# WIZ850io_SCH_V100.net
KiCad netlist of a schematic drawn in Altium Designer
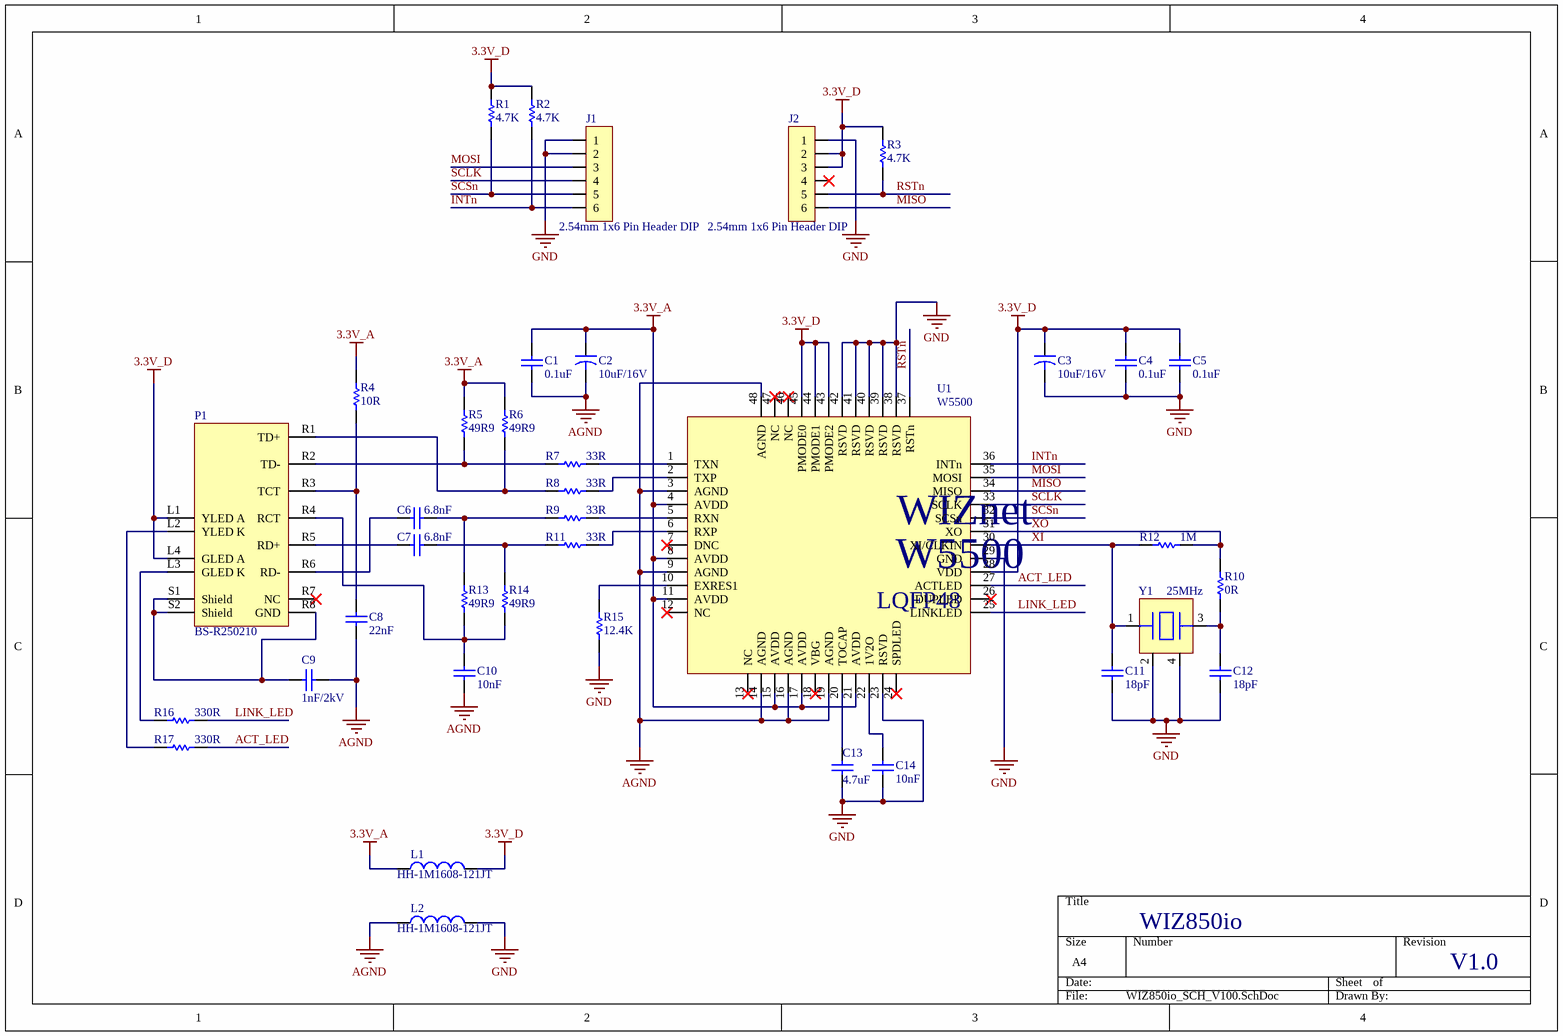
[diagram p0: WIZ850io_SCH_V100.SchDoc]

(export (version "E")
  (design (tool "Eeschema 10.0.6"))
  (components
    (comp (ref "C1")
      (value "0.1uF")
      (footprint "CAP-0402")
      (description "Ceramic CAP 0402(1005)")
      (libsource (lib "Scott_lib") (part "CAP-0402"))
    )
    (comp (ref "C2")
      (value "10uF/16V")
      (footprint "CAP-A Size")
      (description "Tantla CAP A Size EIA/IECQ 3216")
      (libsource (lib "Scott_lib") (part "CAP-A Size"))
    )
    (comp (ref "C3")
      (value "10uF/16V")
      (footprint "CAP-A Size")
      (description "Tantla CAP A Size EIA/IECQ 3216")
      (libsource (lib "Scott_lib") (part "CAP-A Size"))
    )
    (comp (ref "C4")
      (value "0.1uF")
      (footprint "CAP-0402")
      (description "Ceramic CAP 0402(1005)")
      (libsource (lib "Scott_lib") (part "CAP-0402"))
    )
    (comp (ref "C5")
      (value "0.1uF")
      (footprint "CAP-0402")
      (description "Ceramic CAP 0402(1005)")
      (libsource (lib "Scott_lib") (part "CAP-0402"))
    )
    (comp (ref "C6")
      (value "6.8nF")
      (footprint "CAP-0402")
      (description "Ceramic CAP 0402(1005)")
      (libsource (lib "Scott_lib") (part "CAP-0402"))
    )
    (comp (ref "C7")
      (value "6.8nF")
      (footprint "CAP-0402")
      (description "Ceramic CAP 0402(1005)")
      (libsource (lib "Scott_lib") (part "CAP-0402"))
    )
    (comp (ref "C8")
      (value "22nF")
      (footprint "CAP-0402")
      (description "Ceramic CAP 0402(1005)")
      (libsource (lib "Scott_lib") (part "CAP-0402"))
    )
    (comp (ref "C9")
      (value "1nF/2kV")
      (footprint "CAP-1808")
      (description "Ceramic CAP 1808(4520)")
      (libsource (lib "Scott_lib") (part "CAP-1808"))
    )
    (comp (ref "C10")
      (value "10nF")
      (footprint "CAP-0402")
      (description "Ceramic CAP 0402(1005)")
      (libsource (lib "Scott_lib") (part "CAP-0402"))
    )
    (comp (ref "C11")
      (value "18pF")
      (footprint "CAP-0402")
      (description "Ceramic CAP 0402(1005)")
      (libsource (lib "Scott_lib") (part "CAP-0402"))
    )
    (comp (ref "C12")
      (value "18pF")
      (footprint "CAP-0402")
      (description "Ceramic CAP 0402(1005)")
      (libsource (lib "Scott_lib") (part "CAP-0402"))
    )
    (comp (ref "C13")
      (value "4.7uF")
      (footprint "CAP-0805")
      (description "Ceramic CAP 0402(1005)")
      (libsource (lib "Scott_lib") (part "CAP-0402"))
    )
    (comp (ref "C14")
      (value "10nF")
      (footprint "CAP-0402")
      (description "Ceramic CAP 0805(2012)")
      (libsource (lib "Scott_lib") (part "CAP-0805"))
    )
    (comp (ref "J1")
      (value "2.54mm 1x6 Pin Header DIP")
      (footprint "IDC-1X6")
      (libsource (lib "") (part "2.54mm 1x6 Pin Header DIP_1"))
    )
    (comp (ref "J2")
      (value "2.54mm 1x6 Pin Header DIP")
      (footprint "IDC-1X6")
      (libsource (lib "Scott_lib") (part "2.54mm 1x6 Pin Header DIP"))
    )
    (comp (ref "L1")
      (value "HH-1M1608-121JT")
      (footprint "IND-0603")
      (description "Inductor 0603(1608)")
      (libsource (lib "Scott_lib") (part "IND-0603"))
    )
    (comp (ref "L2")
      (value "HH-1M1608-121JT")
      (footprint "IND-0603")
      (description "Inductor 0603(1608)")
      (libsource (lib "Scott_lib") (part "IND-0603"))
    )
    (comp (ref "P1")
      (value "BS-R250210")
      (footprint "BS-R250210")
      (libsource (lib "Scott_lib") (part "BS-R250210"))
    )
    (comp (ref "R1")
      (value "4.7K")
      (footprint "RES-0402")
      (description "RES-0402")
      (libsource (lib "Scott_lib") (part "RES-0402"))
    )
    (comp (ref "R2")
      (value "4.7K")
      (footprint "RES-0402")
      (description "RES-0402")
      (libsource (lib "Scott_lib") (part "RES-0402"))
    )
    (comp (ref "R3")
      (value "4.7K")
      (footprint "RES-0402")
      (description "RES-0402")
      (libsource (lib "Scott_lib") (part "RES-0402"))
    )
    (comp (ref "R4")
      (value "10R")
      (footprint "RES-0402")
      (description "RES-0402")
      (libsource (lib "Scott_lib") (part "RES-0402"))
    )
    (comp (ref "R5")
      (value "49R9")
      (footprint "RES-0402")
      (description "RES-0402")
      (libsource (lib "Scott_lib") (part "RES-0402"))
    )
    (comp (ref "R6")
      (value "49R9")
      (footprint "RES-0402")
      (description "RES-0402")
      (libsource (lib "Scott_lib") (part "RES-0402"))
    )
    (comp (ref "R7")
      (value "33R")
      (footprint "RES-0402")
      (description "RES-0402")
      (libsource (lib "Scott_lib") (part "RES-0402"))
    )
    (comp (ref "R8")
      (value "33R")
      (footprint "RES-0402")
      (description "RES-0402")
      (libsource (lib "Scott_lib") (part "RES-0402"))
    )
    (comp (ref "R9")
      (value "33R")
      (footprint "RES-0402")
      (description "RES-0402")
      (libsource (lib "Scott_lib") (part "RES-0402"))
    )
    (comp (ref "R10")
      (value "0R")
      (footprint "RES-0402")
      (description "RES-0402")
      (libsource (lib "Scott_lib") (part "RES-0402"))
    )
    (comp (ref "R11")
      (value "33R")
      (footprint "RES-0402")
      (description "RES-0402")
      (libsource (lib "Scott_lib") (part "RES-0402"))
    )
    (comp (ref "R12")
      (value "1M")
      (footprint "RES-0402")
      (description "RES-0402")
      (libsource (lib "Scott_lib") (part "RES-0402"))
    )
    (comp (ref "R13")
      (value "49R9")
      (footprint "RES-0402")
      (description "RES-0402")
      (libsource (lib "Scott_lib") (part "RES-0402"))
    )
    (comp (ref "R14")
      (value "49R9")
      (footprint "RES-0402")
      (description "RES-0402")
      (libsource (lib "Scott_lib") (part "RES-0402"))
    )
    (comp (ref "R15")
      (value "12.4K")
      (footprint "RES-0402")
      (description "RES-0402")
      (libsource (lib "Scott_lib") (part "RES-0402"))
    )
    (comp (ref "R16")
      (value "330R")
      (footprint "RES-0402")
      (description "RES-0402")
      (libsource (lib "Scott_lib") (part "RES-0402"))
    )
    (comp (ref "R17")
      (value "330R")
      (footprint "RES-0402")
      (description "RES-0402")
      (libsource (lib "Scott_lib") (part "RES-0402"))
    )
    (comp (ref "U1")
      (value "W5500")
      (footprint "WIZnet W5500")
      (description "WIZnet W5500")
      (libsource (lib "WIZnet Open-source Hardware Library V1.0") (part "W5500"))
    )
    (comp (ref "Y1")
      (value "25MHz")
      (footprint "OSC-82J0626")
      (description "X-tal 25MHz,3.2x2.5 SMD, CL=18pF")
      (libsource (lib "Scott_lib") (part "OSC-82J0626-25MHz"))
    )
  )
  (nets
    (net (code "1") (name "/ACT_LED") (class "Default")
      (node (ref "R17") (pin "2") (pinfunction "2_2") (pintype "passive"))
      (node (ref "U1") (pin "27") (pinfunction "ACTLED_27") (pintype "passive"))
    )
    (net (code "2") (name "/INTn") (class "Default")
      (node (ref "J1") (pin "6") (pinfunction "6_6") (pintype "passive"))
      (node (ref "R2") (pin "1") (pinfunction "1_1") (pintype "passive"))
      (node (ref "U1") (pin "36") (pinfunction "INTn_36") (pintype "passive"))
    )
    (net (code "3") (name "/LINK_LED") (class "Default")
      (node (ref "R16") (pin "2") (pinfunction "2_2") (pintype "passive"))
      (node (ref "U1") (pin "25") (pinfunction "LINKLED_25") (pintype "passive"))
    )
    (net (code "4") (name "/MISO") (class "Default")
      (node (ref "J2") (pin "6") (pinfunction "6_6") (pintype "passive"))
      (node (ref "U1") (pin "34") (pinfunction "MISO_34") (pintype "passive"))
    )
    (net (code "5") (name "/MOSI") (class "Default")
      (node (ref "J1") (pin "3") (pinfunction "3_3") (pintype "passive"))
      (node (ref "U1") (pin "35") (pinfunction "MOSI_35") (pintype "passive"))
    )
    (net (code "6") (name "/RSTn") (class "Default")
      (node (ref "J2") (pin "5") (pinfunction "5_5") (pintype "passive"))
      (node (ref "R3") (pin "1") (pinfunction "1_1") (pintype "passive"))
      (node (ref "U1") (pin "37") (pinfunction "RSTn_37") (pintype "passive"))
    )
    (net (code "7") (name "/SCLK") (class "Default")
      (node (ref "J1") (pin "4") (pinfunction "4_4") (pintype "passive"))
      (node (ref "U1") (pin "33") (pinfunction "SCLK_33") (pintype "passive"))
    )
    (net (code "8") (name "/SCSn") (class "Default")
      (node (ref "J1") (pin "5") (pinfunction "5_5") (pintype "passive"))
      (node (ref "R1") (pin "1") (pinfunction "1_1") (pintype "passive"))
      (node (ref "U1") (pin "32") (pinfunction "SCSn_32") (pintype "passive"))
    )
    (net (code "9") (name "/XI") (class "Default")
      (node (ref "C11") (pin "2") (pinfunction "2_2") (pintype "passive"))
      (node (ref "R12") (pin "1") (pinfunction "1_1") (pintype "passive"))
      (node (ref "U1") (pin "30") (pinfunction "XI/CLKIN_30") (pintype "passive"))
      (node (ref "Y1") (pin "1") (pinfunction "1_1") (pintype "passive"))
    )
    (net (code "10") (name "/XO") (class "Default")
      (node (ref "R10") (pin "2") (pinfunction "2_2") (pintype "passive"))
      (node (ref "R12") (pin "2") (pinfunction "2_2") (pintype "passive"))
      (node (ref "U1") (pin "31") (pinfunction "XO_31") (pintype "passive"))
    )
    (net (code "11") (name "3.3V_A") (class "Default")
      (node (ref "C1") (pin "2") (pinfunction "2_2") (pintype "passive"))
      (node (ref "C2") (pin "1") (pinfunction "1_1") (pintype "passive"))
      (node (ref "L1") (pin "1") (pinfunction "1_1") (pintype "passive"))
      (node (ref "R4") (pin "2") (pinfunction "2_2") (pintype "passive"))
      (node (ref "R5") (pin "2") (pinfunction "2_2") (pintype "passive"))
      (node (ref "R6") (pin "2") (pinfunction "2_2") (pintype "passive"))
      (node (ref "U1") (pin "11") (pinfunction "AVDD_11") (pintype "passive"))
      (node (ref "U1") (pin "15") (pinfunction "AVDD_15") (pintype "passive"))
      (node (ref "U1") (pin "17") (pinfunction "AVDD_17") (pintype "passive"))
      (node (ref "U1") (pin "21") (pinfunction "AVDD_21") (pintype "passive"))
      (node (ref "U1") (pin "4") (pinfunction "AVDD_4") (pintype "passive"))
      (node (ref "U1") (pin "8") (pinfunction "AVDD_8") (pintype "passive"))
    )
    (net (code "12") (name "3.3V_D") (class "Default")
      (node (ref "C3") (pin "1") (pinfunction "1_1") (pintype "passive"))
      (node (ref "C4") (pin "2") (pinfunction "2_2") (pintype "passive"))
      (node (ref "C5") (pin "2") (pinfunction "2_2") (pintype "passive"))
      (node (ref "J2") (pin "2") (pinfunction "2_2") (pintype "passive"))
      (node (ref "J2") (pin "3") (pinfunction "3_3") (pintype "passive"))
      (node (ref "L1") (pin "2") (pinfunction "2_2") (pintype "passive"))
      (node (ref "P1") (pin "L1") (pinfunction "YLED_A_L1") (pintype "passive"))
      (node (ref "P1") (pin "L4") (pinfunction "GLED_A_L4") (pintype "passive"))
      (node (ref "R1") (pin "2") (pinfunction "2_2") (pintype "passive"))
      (node (ref "R2") (pin "2") (pinfunction "2_2") (pintype "passive"))
      (node (ref "R3") (pin "2") (pinfunction "2_2") (pintype "passive"))
      (node (ref "U1") (pin "28") (pinfunction "VDD_28") (pintype "passive"))
      (node (ref "U1") (pin "43") (pinfunction "PMODE2_43") (pintype "passive"))
      (node (ref "U1") (pin "44") (pinfunction "PMODE1_44") (pintype "passive"))
      (node (ref "U1") (pin "45") (pinfunction "PMODE0_45") (pintype "passive"))
    )
    (net (code "13") (name "AGND") (class "Default")
      (node (ref "C1") (pin "1") (pinfunction "1_1") (pintype "passive"))
      (node (ref "C10") (pin "1") (pinfunction "1_1") (pintype "passive"))
      (node (ref "C2") (pin "2") (pinfunction "2_2") (pintype "passive"))
      (node (ref "C8") (pin "1") (pinfunction "1_1") (pintype "passive"))
      (node (ref "C9") (pin "1") (pinfunction "1_1") (pintype "passive"))
      (node (ref "L2") (pin "1") (pinfunction "1_1") (pintype "passive"))
      (node (ref "U1") (pin "14") (pinfunction "AGND_14") (pintype "passive"))
      (node (ref "U1") (pin "16") (pinfunction "AGND_16") (pintype "passive"))
      (node (ref "U1") (pin "19") (pinfunction "AGND_19") (pintype "passive"))
      (node (ref "U1") (pin "3") (pinfunction "AGND_3") (pintype "passive"))
      (node (ref "U1") (pin "48") (pinfunction "AGND_48") (pintype "passive"))
      (node (ref "U1") (pin "9") (pinfunction "AGND_9") (pintype "passive"))
    )
    (net (code "14") (name "GND") (class "Default")
      (node (ref "C11") (pin "1") (pinfunction "1_1") (pintype "passive"))
      (node (ref "C12") (pin "1") (pinfunction "1_1") (pintype "passive"))
      (node (ref "C13") (pin "1") (pinfunction "1_1") (pintype "passive"))
      (node (ref "C14") (pin "1") (pinfunction "1_1") (pintype "passive"))
      (node (ref "C3") (pin "2") (pinfunction "2_2") (pintype "passive"))
      (node (ref "C4") (pin "1") (pinfunction "1_1") (pintype "passive"))
      (node (ref "C5") (pin "1") (pinfunction "1_1") (pintype "passive"))
      (node (ref "J1") (pin "1") (pinfunction "1_1") (pintype "passive"))
      (node (ref "J1") (pin "2") (pinfunction "2_2") (pintype "passive"))
      (node (ref "J2") (pin "1") (pinfunction "1_1") (pintype "passive"))
      (node (ref "L2") (pin "2") (pinfunction "2_2") (pintype "passive"))
      (node (ref "R15") (pin "1") (pinfunction "1_1") (pintype "passive"))
      (node (ref "U1") (pin "23") (pinfunction "RSVD_23") (pintype "passive"))
      (node (ref "U1") (pin "29") (pinfunction "GND_29") (pintype "passive"))
      (node (ref "U1") (pin "38") (pinfunction "RSVD_38") (pintype "passive"))
      (node (ref "U1") (pin "39") (pinfunction "RSVD_39") (pintype "passive"))
      (node (ref "U1") (pin "40") (pinfunction "RSVD_40") (pintype "passive"))
      (node (ref "U1") (pin "41") (pinfunction "RSVD_41") (pintype "passive"))
      (node (ref "U1") (pin "42") (pinfunction "RSVD_42") (pintype "passive"))
      (node (ref "Y1") (pin "2") (pinfunction "2_2") (pintype "passive"))
      (node (ref "Y1") (pin "4") (pinfunction "4_4") (pintype "passive"))
    )
    (net (code "15") (name "Net-(C6-Pad2)") (class "Default")
      (node (ref "C6") (pin "2") (pinfunction "2_2") (pintype "passive"))
      (node (ref "R13") (pin "2") (pinfunction "2_2") (pintype "passive"))
      (node (ref "R9") (pin "1") (pinfunction "1_1") (pintype "passive"))
    )
    (net (code "16") (name "Net-(C7-Pad2)") (class "Default")
      (node (ref "C7") (pin "2") (pinfunction "2_2") (pintype "passive"))
      (node (ref "R11") (pin "1") (pinfunction "1_1") (pintype "passive"))
      (node (ref "R14") (pin "2") (pinfunction "2_2") (pintype "passive"))
    )
    (net (code "17") (name "Net-(C12-Pad2)") (class "Default")
      (node (ref "C12") (pin "2") (pinfunction "2_2") (pintype "passive"))
      (node (ref "R10") (pin "1") (pinfunction "1_1") (pintype "passive"))
      (node (ref "Y1") (pin "3") (pinfunction "3_3") (pintype "passive"))
    )
    (net (code "18") (name "Net-(P1-GLED_K)") (class "Default")
      (node (ref "P1") (pin "L3") (pinfunction "GLED_K_L3") (pintype "passive"))
      (node (ref "R16") (pin "1") (pinfunction "1_1") (pintype "passive"))
    )
    (net (code "19") (name "Net-(P1-GND)") (class "Default")
      (node (ref "C9") (pin "2") (pinfunction "2_2") (pintype "passive"))
      (node (ref "P1") (pin "R8") (pinfunction "GND_R8") (pintype "passive"))
      (node (ref "P1") (pin "S1") (pinfunction "Shield_S1") (pintype "passive"))
      (node (ref "P1") (pin "S2") (pinfunction "Shield_S2") (pintype "passive"))
    )
    (net (code "20") (name "Net-(P1-RCT)") (class "Default")
      (node (ref "C10") (pin "2") (pinfunction "2_2") (pintype "passive"))
      (node (ref "P1") (pin "R4") (pinfunction "RCT_R4") (pintype "passive"))
      (node (ref "R13") (pin "1") (pinfunction "1_1") (pintype "passive"))
      (node (ref "R14") (pin "1") (pinfunction "1_1") (pintype "passive"))
    )
    (net (code "21") (name "Net-(P1-RD+)") (class "Default")
      (node (ref "C7") (pin "1") (pinfunction "1_1") (pintype "passive"))
      (node (ref "P1") (pin "R5") (pinfunction "RD+_R5") (pintype "passive"))
    )
    (net (code "22") (name "Net-(P1-RD-)") (class "Default")
      (node (ref "C6") (pin "1") (pinfunction "1_1") (pintype "passive"))
      (node (ref "P1") (pin "R6") (pinfunction "RD-_R6") (pintype "passive"))
    )
    (net (code "23") (name "Net-(P1-TCT)") (class "Default")
      (node (ref "C8") (pin "2") (pinfunction "2_2") (pintype "passive"))
      (node (ref "P1") (pin "R3") (pinfunction "TCT_R3") (pintype "passive"))
      (node (ref "R4") (pin "1") (pinfunction "1_1") (pintype "passive"))
    )
    (net (code "24") (name "Net-(P1-TD+)") (class "Default")
      (node (ref "P1") (pin "R1") (pinfunction "TD+_R1") (pintype "passive"))
      (node (ref "R6") (pin "1") (pinfunction "1_1") (pintype "passive"))
      (node (ref "R8") (pin "1") (pinfunction "1_1") (pintype "passive"))
    )
    (net (code "25") (name "Net-(P1-TD-)") (class "Default")
      (node (ref "P1") (pin "R2") (pinfunction "TD-_R2") (pintype "passive"))
      (node (ref "R5") (pin "1") (pinfunction "1_1") (pintype "passive"))
      (node (ref "R7") (pin "1") (pinfunction "1_1") (pintype "passive"))
    )
    (net (code "26") (name "Net-(P1-YLED_K)") (class "Default")
      (node (ref "P1") (pin "L2") (pinfunction "YLED_K_L2") (pintype "passive"))
      (node (ref "R17") (pin "1") (pinfunction "1_1") (pintype "passive"))
    )
    (net (code "27") (name "Net-(U1-1V2O)") (class "Default")
      (node (ref "C14") (pin "2") (pinfunction "2_2") (pintype "passive"))
      (node (ref "U1") (pin "22") (pinfunction "1V2O_22") (pintype "passive"))
    )
    (net (code "28") (name "Net-(U1-EXRES1)") (class "Default")
      (node (ref "R15") (pin "2") (pinfunction "2_2") (pintype "passive"))
      (node (ref "U1") (pin "10") (pinfunction "EXRES1_10") (pintype "passive"))
    )
    (net (code "29") (name "Net-(U1-RXN)") (class "Default")
      (node (ref "R9") (pin "2") (pinfunction "2_2") (pintype "passive"))
      (node (ref "U1") (pin "5") (pinfunction "RXN_5") (pintype "passive"))
    )
    (net (code "30") (name "Net-(U1-RXP)") (class "Default")
      (node (ref "R11") (pin "2") (pinfunction "2_2") (pintype "passive"))
      (node (ref "U1") (pin "6") (pinfunction "RXP_6") (pintype "passive"))
    )
    (net (code "31") (name "Net-(U1-TOCAP)") (class "Default")
      (node (ref "C13") (pin "2") (pinfunction "2_2") (pintype "passive"))
      (node (ref "U1") (pin "20") (pinfunction "TOCAP_20") (pintype "passive"))
    )
    (net (code "32") (name "Net-(U1-TXN)") (class "Default")
      (node (ref "R7") (pin "2") (pinfunction "2_2") (pintype "passive"))
      (node (ref "U1") (pin "1") (pinfunction "TXN_1") (pintype "passive"))
    )
    (net (code "33") (name "Net-(U1-TXP)") (class "Default")
      (node (ref "R8") (pin "2") (pinfunction "2_2") (pintype "passive"))
      (node (ref "U1") (pin "2") (pinfunction "TXP_2") (pintype "passive"))
    )
    (net (code "34") (name "unconnected-(J2-Pad4)") (class "Default")
      (node (ref "J2") (pin "4") (pinfunction "4_4") (pintype "passive+no_connect"))
    )
    (net (code "35") (name "unconnected-(P1-NC-PadR7)") (class "Default")
      (node (ref "P1") (pin "R7") (pinfunction "NC_R7") (pintype "passive+no_connect"))
    )
    (net (code "36") (name "unconnected-(U1-DNC-Pad7)") (class "Default")
      (node (ref "U1") (pin "7") (pinfunction "DNC_7") (pintype "passive+no_connect"))
    )
    (net (code "37") (name "unconnected-(U1-DUPLED-Pad26)") (class "Default")
      (node (ref "U1") (pin "26") (pinfunction "DUPLED_26") (pintype "passive+no_connect"))
    )
    (net (code "38") (name "unconnected-(U1-NC-Pad12)") (class "Default")
      (node (ref "U1") (pin "12") (pinfunction "NC_12") (pintype "passive+no_connect"))
    )
    (net (code "39") (name "unconnected-(U1-NC-Pad13)") (class "Default")
      (node (ref "U1") (pin "13") (pinfunction "NC_13") (pintype "passive+no_connect"))
    )
    (net (code "40") (name "unconnected-(U1-NC-Pad46)") (class "Default")
      (node (ref "U1") (pin "46") (pinfunction "NC_46") (pintype "passive+no_connect"))
    )
    (net (code "41") (name "unconnected-(U1-NC-Pad47)") (class "Default")
      (node (ref "U1") (pin "47") (pinfunction "NC_47") (pintype "passive+no_connect"))
    )
    (net (code "42") (name "unconnected-(U1-SPDLED-Pad24)") (class "Default")
      (node (ref "U1") (pin "24") (pinfunction "SPDLED_24") (pintype "passive+no_connect"))
    )
    (net (code "43") (name "unconnected-(U1-VBG-Pad18)") (class "Default")
      (node (ref "U1") (pin "18") (pinfunction "VBG_18") (pintype "passive+no_connect"))
    )
  )
)
